# Sheet1.net
KiCad netlist of a schematic drawn in Altium Designer
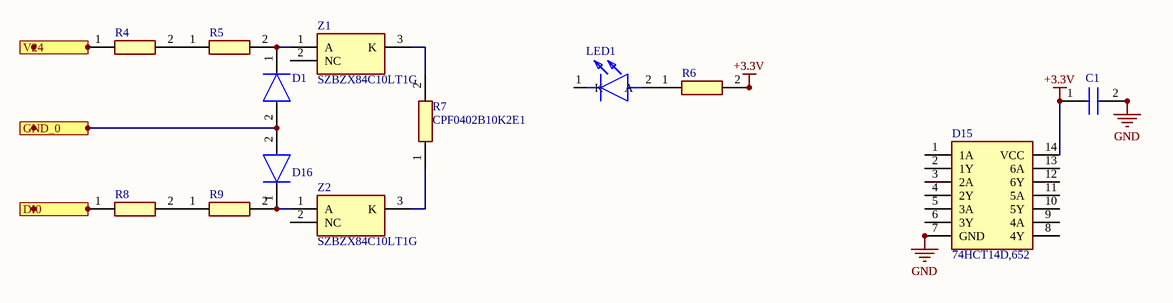
[diagram p0: Sheet1.SchDoc]

(export (version "E")
  (design (tool "Eeschema 10.0.6"))
  (components
    (comp (ref "C1")
      (value "04023C104JAT2A")
      (footprint "SamacSys:CAPC1005X56N")
      (description "Capacitor")
      (fields
        (field (name "MOUSER PART NUMBER") "581-04023C104JAT2A")
        (field (name "RS PART NUMBER") "1356696")
      )
      (libsource (lib "*") (part "04023C104JAT2A"))
    )
    (comp (ref "D1")
      (value "SMF18AT1G")
      (footprint "SamacSys:SODFL3616X98N")
      (description "Diode")
      (libsource (lib "*") (part "SMF18AT1G"))
    )
    (comp (ref "D15")
      (value "74HCT14D,652")
      (footprint "SamacSys:SOIC127P600X175-14N")
      (description "Integrated Circuit")
      (fields (field (name "MOUSER PART NUMBER") "771-HCT14D652") (field (name "RS PART NUMBER") "1130641P"))
      (libsource (lib "*") (part "74HCT14D,652"))
    )
    (comp (ref "D16")
      (value "SMF18AT1G")
      (footprint "SamacSys:SODFL3616X98N")
      (description "Diode")
      (libsource (lib "*") (part "SMF18AT1G"))
    )
    (comp (ref "LED1")
      (value "151034GS03000")
      (footprint "SamacSys:151034GS03000")
      (description "LED")
      (fields (field (name "RS PART NUMBER") "9010930"))
      (libsource (lib "*") (part "151034GS03000"))
    )
    (comp (ref "R4")
      (value "CPF0805B330RE")
      (footprint "SamacSys:RESC2012X65N")
      (description "Resistor")
      (fields (field (name "RS PART NUMBER") "6662471"))
      (libsource (lib "*") (part "CPF0805B330RE"))
    )
    (comp (ref "R5")
      (value "CPF0805B330RE")
      (footprint "SamacSys:RESC2012X65N")
      (description "Resistor")
      (fields (field (name "RS PART NUMBER") "6662471"))
      (libsource (lib "*") (part "CPF0805B330RE"))
    )
    (comp (ref "R6")
      (value "CPF0402B300RE")
      (footprint "SamacSys:RESC1005X35N")
      (description "Resistor")
      (fields (field (name "RS PART NUMBER") "6661327"))
      (libsource (lib "*") (part "CPF0402B300RE"))
    )
    (comp (ref "R7")
      (value "CPF0402B10K2E1")
      (footprint "SamacSys:RESC1005X35N")
      (description "Resistor")
      (fields
        (field (name "MOUSER PART NUMBER") "279-CPF0402B10K2E1")
        (field (name "RS PART NUMBER") "7015028")
      )
      (libsource (lib "*") (part "CPF0402B10K2E1"))
    )
    (comp (ref "R8")
      (value "CPF0805B330RE")
      (footprint "SamacSys:RESC2012X65N")
      (description "Resistor")
      (fields (field (name "RS PART NUMBER") "6662471"))
      (libsource (lib "*") (part "CPF0805B330RE"))
    )
    (comp (ref "R9")
      (value "CPF0805B330RE")
      (footprint "SamacSys:RESC2012X65N")
      (description "Resistor")
      (fields (field (name "RS PART NUMBER") "6662471"))
      (libsource (lib "*") (part "CPF0805B330RE"))
    )
    (comp (ref "Z1")
      (value "SZBZX84C10LT1G")
      (footprint "SamacSys:SOT96P237X111-3N")
      (description "Zener Diode")
      (fields
        (field (name "MOUSER PART NUMBER") "863-SZBZX84C10LT1G")
        (field (name "RS PART NUMBER") "8052914")
      )
      (libsource (lib "*") (part "SZBZX84C10LT1G"))
    )
    (comp (ref "Z2")
      (value "SZBZX84C10LT1G")
      (footprint "SamacSys:SOT96P237X111-3N")
      (description "Zener Diode")
      (fields
        (field (name "MOUSER PART NUMBER") "863-SZBZX84C10LT1G")
        (field (name "RS PART NUMBER") "8052914")
      )
      (libsource (lib "*") (part "SZBZX84C10LT1G"))
    )
  )
  (nets
    (net (code "1") (name "+3.3V") (class "Default")
      (node (ref "C1") (pin "1") (pinfunction "1_1") (pintype "passive"))
      (node (ref "D15") (pin "14") (pinfunction "VCC_14") (pintype "passive"))
      (node (ref "R6") (pin "2") (pinfunction "2_2") (pintype "passive"))
    )
    (net (code "2") (name "/DI0") (class "Default")
      (node (ref "R8") (pin "1") (pinfunction "1_1") (pintype "passive"))
    )
    (net (code "3") (name "/GND0") (class "Default")
      (node (ref "D1") (pin "2") (pinfunction "A_2") (pintype "passive"))
      (node (ref "D16") (pin "2") (pinfunction "A_2") (pintype "passive"))
    )
    (net (code "4") (name "/V24") (class "Default")
      (node (ref "R4") (pin "1") (pinfunction "1_1") (pintype "passive"))
    )
    (net (code "5") (name "GND") (class "Default")
      (node (ref "C1") (pin "2") (pinfunction "2_2") (pintype "passive"))
      (node (ref "D15") (pin "7") (pinfunction "GND_7") (pintype "passive"))
    )
    (net (code "6") (name "Net-(D1-K)") (class "Default")
      (node (ref "D1") (pin "1") (pinfunction "K_1") (pintype "passive"))
      (node (ref "R5") (pin "2") (pinfunction "2_2") (pintype "passive"))
      (node (ref "Z1") (pin "1") (pinfunction "A_1") (pintype "passive"))
    )
    (net (code "7") (name "Net-(D16-K)") (class "Default")
      (node (ref "D16") (pin "1") (pinfunction "K_1") (pintype "passive"))
      (node (ref "R9") (pin "2") (pinfunction "2_2") (pintype "passive"))
      (node (ref "Z2") (pin "1") (pinfunction "A_1") (pintype "passive"))
    )
    (net (code "8") (name "Net-(LED1-A)") (class "Default")
      (node (ref "LED1") (pin "2") (pinfunction "A_2") (pintype "passive"))
      (node (ref "R6") (pin "1") (pinfunction "1_1") (pintype "passive"))
    )
    (net (code "9") (name "Net-(R4-Pad2)") (class "Default")
      (node (ref "R4") (pin "2") (pinfunction "2_2") (pintype "passive"))
      (node (ref "R5") (pin "1") (pinfunction "1_1") (pintype "passive"))
    )
    (net (code "10") (name "Net-(R8-Pad2)") (class "Default")
      (node (ref "R8") (pin "2") (pinfunction "2_2") (pintype "passive"))
      (node (ref "R9") (pin "1") (pinfunction "1_1") (pintype "passive"))
    )
    (net (code "11") (name "Net-(Z1-K)") (class "Default")
      (node (ref "R7") (pin "2") (pinfunction "2_2") (pintype "passive"))
      (node (ref "Z1") (pin "3") (pinfunction "K_3") (pintype "passive"))
    )
    (net (code "12") (name "Net-(Z2-K)") (class "Default")
      (node (ref "R7") (pin "1") (pinfunction "1_1") (pintype "passive"))
      (node (ref "Z2") (pin "3") (pinfunction "K_3") (pintype "passive"))
    )
    (net (code "13") (name "unconnected-(D15-1A-Pad1)") (class "Default")
      (node (ref "D15") (pin "1") (pinfunction "1A_1") (pintype "passive"))
    )
    (net (code "14") (name "unconnected-(D15-1Y-Pad2)") (class "Default")
      (node (ref "D15") (pin "2") (pinfunction "1Y_2") (pintype "passive"))
    )
    (net (code "15") (name "unconnected-(D15-2A-Pad3)") (class "Default")
      (node (ref "D15") (pin "3") (pinfunction "2A_3") (pintype "passive"))
    )
    (net (code "16") (name "unconnected-(D15-2Y-Pad4)") (class "Default")
      (node (ref "D15") (pin "4") (pinfunction "2Y_4") (pintype "passive"))
    )
    (net (code "17") (name "unconnected-(D15-3A-Pad5)") (class "Default")
      (node (ref "D15") (pin "5") (pinfunction "3A_5") (pintype "passive"))
    )
    (net (code "18") (name "unconnected-(D15-3Y-Pad6)") (class "Default")
      (node (ref "D15") (pin "6") (pinfunction "3Y_6") (pintype "passive"))
    )
    (net (code "19") (name "unconnected-(D15-4A-Pad9)") (class "Default")
      (node (ref "D15") (pin "9") (pinfunction "4A_9") (pintype "passive"))
    )
    (net (code "20") (name "unconnected-(D15-4Y-Pad8)") (class "Default")
      (node (ref "D15") (pin "8") (pinfunction "4Y_8") (pintype "passive"))
    )
    (net (code "21") (name "unconnected-(D15-5A-Pad11)") (class "Default")
      (node (ref "D15") (pin "11") (pinfunction "5A_11") (pintype "passive"))
    )
    (net (code "22") (name "unconnected-(D15-5Y-Pad10)") (class "Default")
      (node (ref "D15") (pin "10") (pinfunction "5Y_10") (pintype "passive"))
    )
    (net (code "23") (name "unconnected-(D15-6A-Pad13)") (class "Default")
      (node (ref "D15") (pin "13") (pinfunction "6A_13") (pintype "passive"))
    )
    (net (code "24") (name "unconnected-(D15-6Y-Pad12)") (class "Default")
      (node (ref "D15") (pin "12") (pinfunction "6Y_12") (pintype "passive"))
    )
    (net (code "25") (name "unconnected-(LED1-K-Pad1)") (class "Default")
      (node (ref "LED1") (pin "1") (pinfunction "K_1") (pintype "passive"))
    )
    (net (code "26") (name "unconnected-(Z1-NC-Pad2)") (class "Default")
      (node (ref "Z1") (pin "2") (pinfunction "NC_2") (pintype "passive"))
    )
    (net (code "27") (name "unconnected-(Z2-NC-Pad2)") (class "Default")
      (node (ref "Z2") (pin "2") (pinfunction "NC_2") (pintype "passive"))
    )
  )
)
